# Schematic.net
KiCad netlist of a schematic drawn in EAGLE
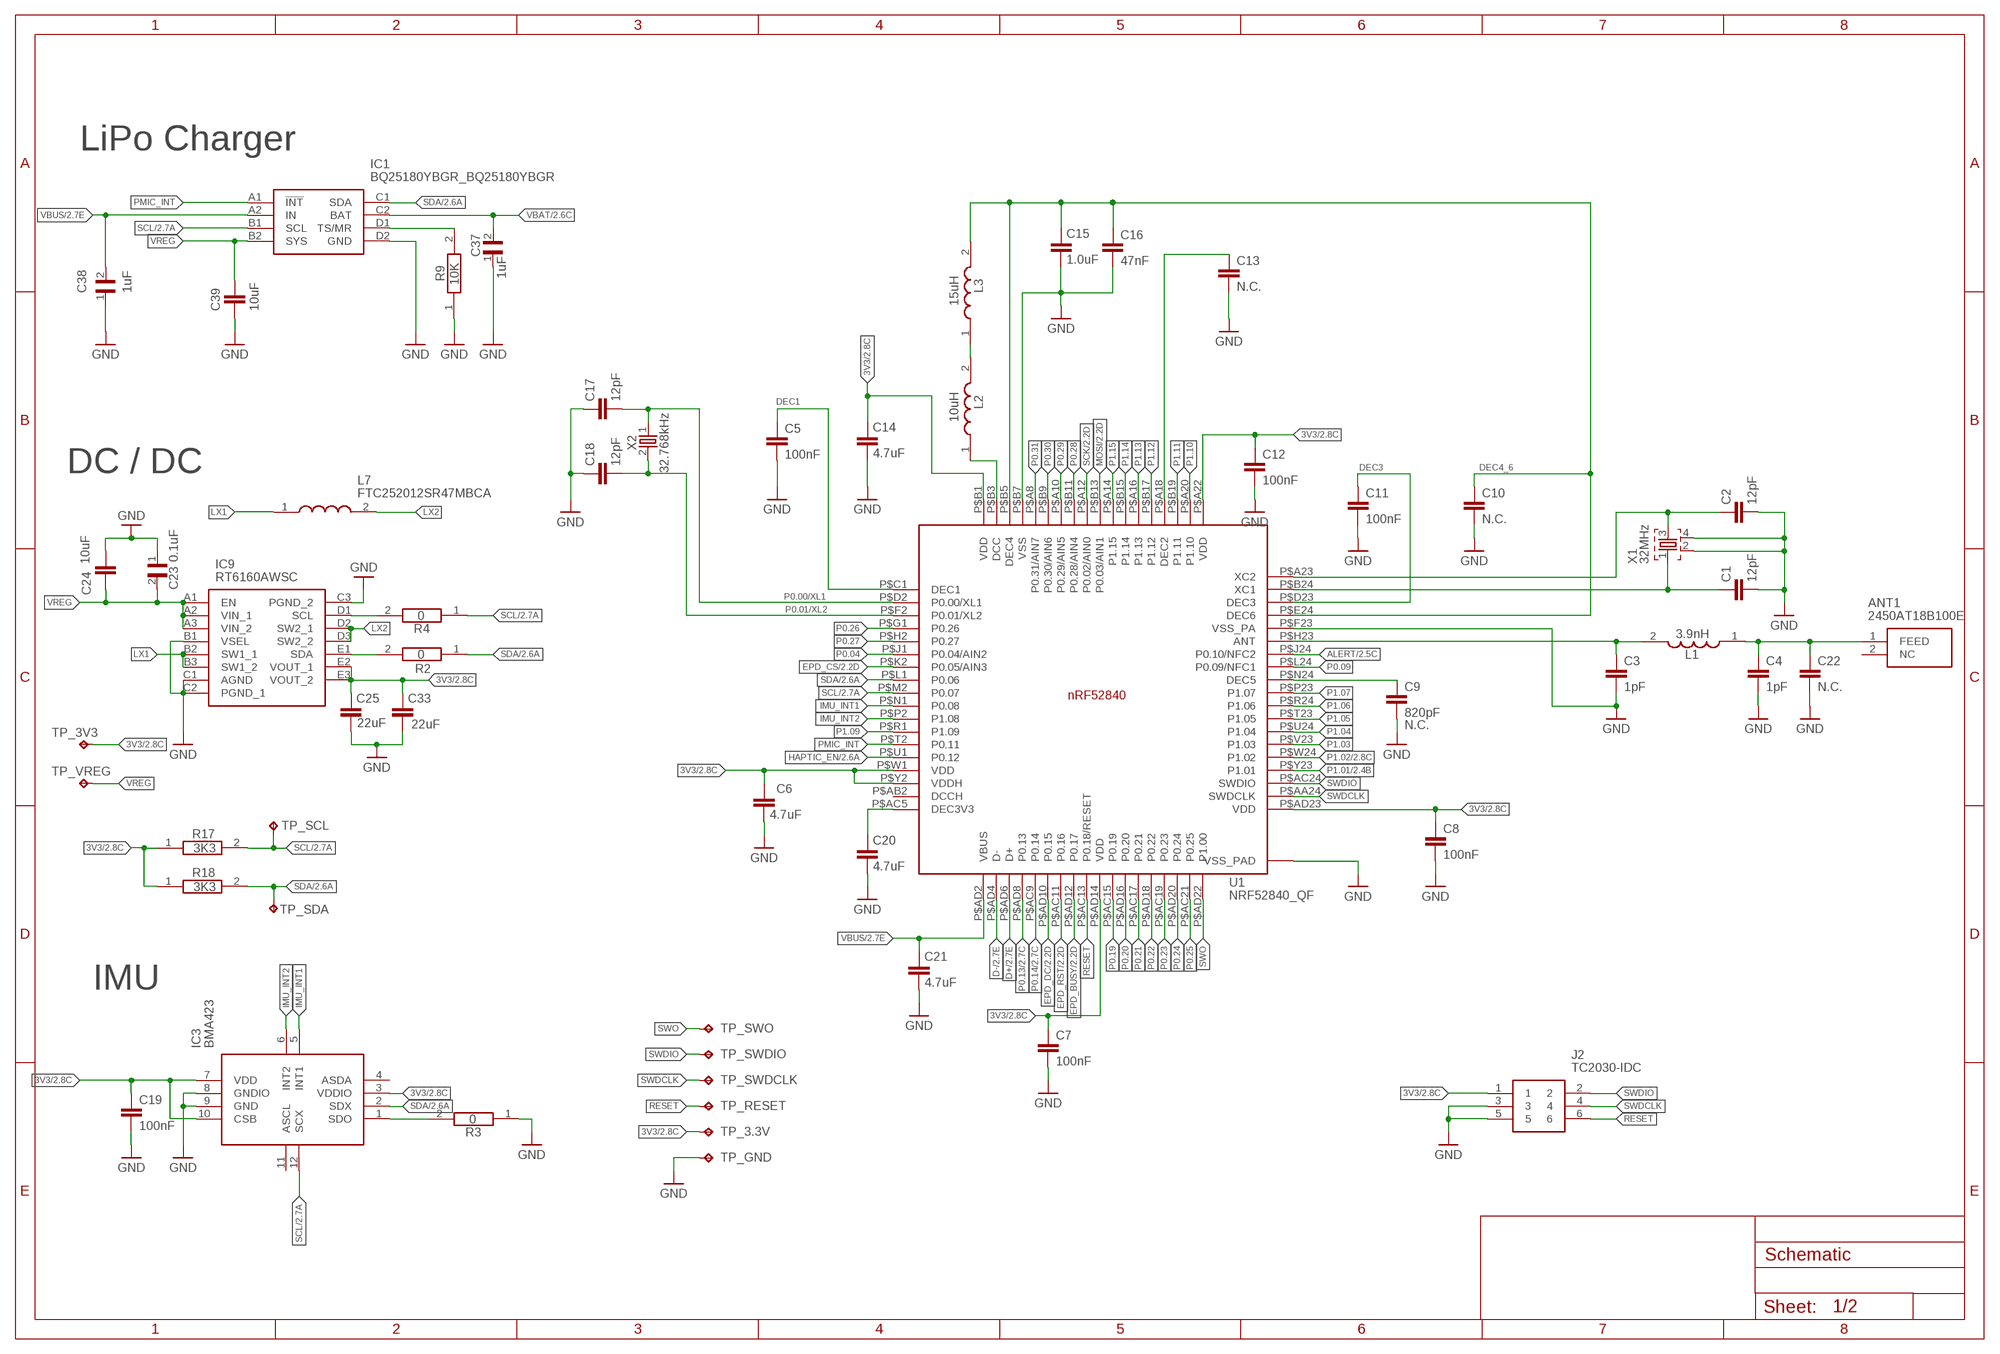
[diagram p0: schematic, sheet 1]
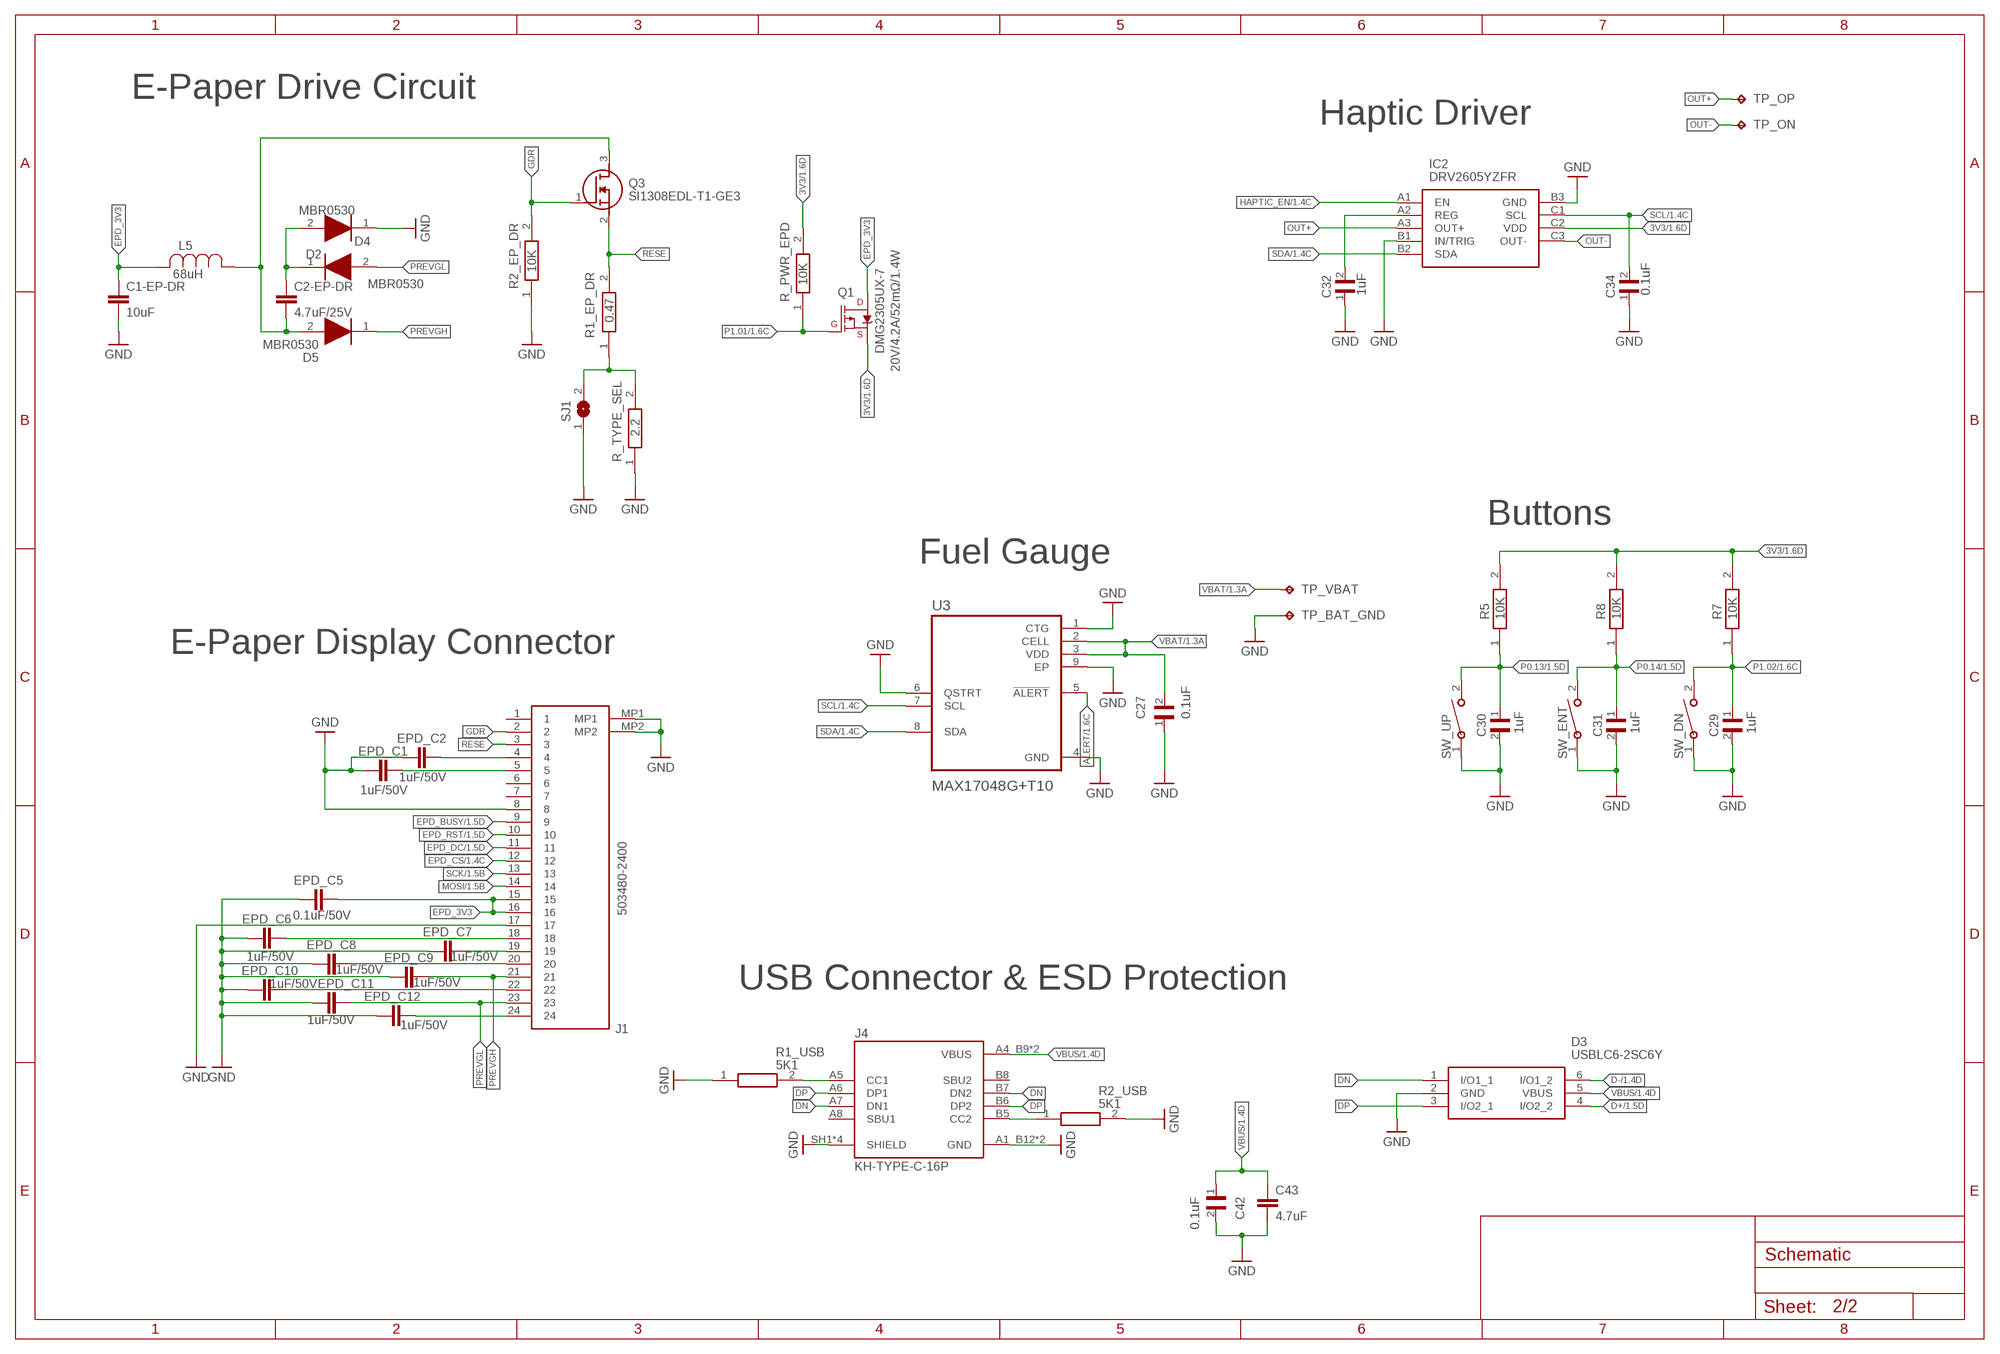
[diagram p1: schematic, sheet 2]

(export (version "E")
  (design (tool "Eeschema 10.0.6"))
  (components
    (comp (ref "C1-EP-DR")
      (value "10uF")
      (footprint "eagle-import:NORDIC_NRF_3_RESC0402_L")
      (libsource (lib "eagle-import") (part "NORDIC_NRF_3_CAPACITOR_0402_L"))
    )
    (comp (ref "C2-EP-DR")
      (value "4.7uF/25V")
      (footprint "eagle-import:NORDIC_NRF_3_RESC0402_L")
      (libsource (lib "eagle-import") (part "NORDIC_NRF_3_CAPACITOR_0402_L"))
    )
    (comp (ref "C27")
      (value "0.1uF")
      (footprint "eagle-import:GRM011R60J152KE01L_2_CAPC0201X13N")
      (fields (field (name "MF") "Murata") (field (name "MP") "GRM011R60J152KE01L"))
      (libsource (lib "eagle-import") (part "GRM011R60J152KE01L_2_GRM011R60J152KE01L"))
    )
    (comp (ref "C29")
      (value "1uF")
      (footprint "eagle-import:GRM011R60J152KE01L_1_0201")
      (libsource (lib "eagle-import") (part "GRM011R60J152KE01L_1_GRM011R60J152KE01L"))
    )
    (comp (ref "C30")
      (value "1uF")
      (footprint "eagle-import:GRM011R60J152KE01L_1_0201")
      (libsource (lib "eagle-import") (part "GRM011R60J152KE01L_1_GRM011R60J152KE01L"))
    )
    (comp (ref "C31")
      (value "1uF")
      (footprint "eagle-import:GRM011R60J152KE01L_1_0201")
      (libsource (lib "eagle-import") (part "GRM011R60J152KE01L_1_GRM011R60J152KE01L"))
    )
    (comp (ref "C32")
      (value "1uF")
      (footprint "eagle-import:GRM011R60J152KE01L_1_0201")
      (libsource (lib "eagle-import") (part "GRM011R60J152KE01L_1_GRM011R60J152KE01L"))
    )
    (comp (ref "C34")
      (value "0.1uF")
      (footprint "eagle-import:GRM011R60J152KE01L_1_0201")
      (libsource (lib "eagle-import") (part "GRM011R60J152KE01L_1_GRM011R60J152KE01L"))
    )
    (comp (ref "C42")
      (value "0.1uF")
      (footprint "eagle-import:GRM011R60J152KE01L_1_0201")
      (libsource (lib "eagle-import") (part "GRM011R60J152KE01L_1_GRM011R60J152KE01L"))
    )
    (comp (ref "C43")
      (value "4.7uF")
      (footprint "eagle-import:NORDIC_NRF_3_RESC0402_L")
      (libsource (lib "eagle-import") (part "NORDIC_NRF_3_CAPACITOR_0402_L"))
    )
    (comp (ref "D2")
      (value "MBR0530")
      (footprint "eagle-import:ESP32_C6_LIBRARY_5_SOD3716X135N")
      (fields (field (name "MF") "ON Semiconductor"))
      (libsource (lib "eagle-import") (part "ESP32_C6_LIBRARY_5_MBR0530"))
    )
    (comp (ref "D3")
      (value "USBLC6-2SC6Y")
      (footprint "eagle-import:ESP32_C6_LIBRARY_3_SOT95P280X145-6N")
      (fields (field (name "MF") "STMicroelectronics"))
      (libsource (lib "eagle-import") (part "ESP32_C6_LIBRARY_3_USBLC6-2SC6Y"))
    )
    (comp (ref "D4")
      (value "MBR0530")
      (footprint "eagle-import:ESP32_C6_LIBRARY_5_SOD3716X135N")
      (fields (field (name "MF") "ON Semiconductor"))
      (libsource (lib "eagle-import") (part "ESP32_C6_LIBRARY_5_MBR0530"))
    )
    (comp (ref "D5")
      (value "MBR0530")
      (footprint "eagle-import:ESP32_C6_LIBRARY_5_SOD3716X135N")
      (fields (field (name "MF") "ON Semiconductor"))
      (libsource (lib "eagle-import") (part "ESP32_C6_LIBRARY_5_MBR0530"))
    )
    (comp (ref "EPD_C1")
      (value "1uF/50V")
      (footprint "eagle-import:NORDIC_NRF_3_RESC0402_L")
      (libsource (lib "eagle-import") (part "NORDIC_NRF_3_CAPACITOR_0402_L"))
    )
    (comp (ref "EPD_C2")
      (value "1uF/50V")
      (footprint "eagle-import:NORDIC_NRF_3_RESC0402_L")
      (libsource (lib "eagle-import") (part "NORDIC_NRF_3_CAPACITOR_0402_L"))
    )
    (comp (ref "EPD_C5")
      (value "0.1uF/50V")
      (footprint "eagle-import:NORDIC_NRF_3_RESC0201_L")
      (libsource (lib "eagle-import") (part "NORDIC_NRF_3_CAPACITOR_0201_L"))
    )
    (comp (ref "EPD_C6")
      (value "1uF/50V")
      (footprint "eagle-import:NORDIC_NRF_3_RESC0402_L")
      (libsource (lib "eagle-import") (part "NORDIC_NRF_3_CAPACITOR_0402_L"))
    )
    (comp (ref "EPD_C7")
      (value "1uF/50V")
      (footprint "eagle-import:NORDIC_NRF_3_RESC0402_L")
      (libsource (lib "eagle-import") (part "NORDIC_NRF_3_CAPACITOR_0402_L"))
    )
    (comp (ref "EPD_C8")
      (value "1uF/50V")
      (footprint "eagle-import:NORDIC_NRF_3_RESC0402_L")
      (libsource (lib "eagle-import") (part "NORDIC_NRF_3_CAPACITOR_0402_L"))
    )
    (comp (ref "EPD_C9")
      (value "1uF/50V")
      (footprint "eagle-import:NORDIC_NRF_3_RESC0402_L")
      (libsource (lib "eagle-import") (part "NORDIC_NRF_3_CAPACITOR_0402_L"))
    )
    (comp (ref "EPD_C10")
      (value "1uF/50V")
      (footprint "eagle-import:NORDIC_NRF_3_RESC0402_L")
      (libsource (lib "eagle-import") (part "NORDIC_NRF_3_CAPACITOR_0402_L"))
    )
    (comp (ref "EPD_C11")
      (value "1uF/50V")
      (footprint "eagle-import:NORDIC_NRF_3_RESC0402_L")
      (libsource (lib "eagle-import") (part "NORDIC_NRF_3_CAPACITOR_0402_L"))
    )
    (comp (ref "EPD_C12")
      (value "1uF/50V")
      (footprint "eagle-import:NORDIC_NRF_3_RESC0402_L")
      (libsource (lib "eagle-import") (part "NORDIC_NRF_3_CAPACITOR_0402_L"))
    )
    (comp (ref "IC2")
      (value "DRV2605YZFR")
      (footprint "eagle-import:DRV2605YZFR_BGA9C50P3X3_144X144X62")
      (libsource (lib "eagle-import") (part "DRV2605YZFR_DRV2605YZFR"))
    )
    (comp (ref "J1")
      (value "503480-2400")
      (footprint "eagle-import:503480-2400_5034802400")
      (fields (field (name "MOUSER_PART_NUMBER") "538-503480-2400"))
      (libsource (lib "eagle-import") (part "503480-2400_503480-2400"))
    )
    (comp (ref "J4")
      (value "KH-TYPE-C-16P")
      (footprint "eagle-import:KH-TYPE-C-16P_KINGHELM_KH-TYPE-C-16P")
      (fields (field (name "MF") "kinghelm"))
      (libsource (lib "eagle-import") (part "KH-TYPE-C-16P_KH-TYPE-C-16P"))
    )
    (comp (ref "L5")
      (value "68uH")
      (footprint "eagle-import:ESP32_C6_LIBRARY_2_IND_4828-WE-TPC_WRE")
      (fields
        (field (name "MANUFACTURER_PART_NUMBER") "744043680")
        (field (name "COPYRIGHT") "Copyright (C) 2024 Ultra Librarian. All rights reserved.")
      )
      (libsource (lib "eagle-import") (part "ESP32_C6_LIBRARY_2_744043680IND_4828-WE-TPC_WRE"))
    )
    (comp (ref "Q1")
      (value "20V/4.2A/52mΩ/1.4W")
      (footprint "eagle-import:ESP32_C6_LIBRARY_4_ESP32_C6_LIBRARY_4_ESP32_C6_LIBRARY_4_ESP32_C6_LIBRARY_4_ESP32_WROVER_SPARKFUN-DISCRETESEMI_SOT23-3")
      (libsource (lib "eagle-import") (part "ESP32_C6_LIBRARY_4_ESP32_WROVER_SPARKFUN-DISCRETESEMI_MOSFET_PCH-DMG2305UX-7"))
    )
    (comp (ref "Q3")
      (value "SI1308EDL-T1-GE3")
      (footprint "eagle-import:ESP32_C6_LIBRARY_6_SOT65P210X110-3N")
      (fields (field (name "MF") "Vishay Siliconix"))
      (libsource (lib "eagle-import") (part "ESP32_C6_LIBRARY_6_SI1308EDL-T1-GE3"))
    )
    (comp (ref "R1_EP_DR")
      (value "0.47")
      (footprint "eagle-import:ERA-1AEB3401C_0201")
      (libsource (lib "eagle-import") (part "ERA-1AEB3401C_CPF0201D7K68C1"))
    )
    (comp (ref "R1_USB")
      (value "5K1")
      (footprint "eagle-import:ERA-1AEB3401C_0201")
      (libsource (lib "eagle-import") (part "ERA-1AEB3401C_CPF0201D7K68C1"))
    )
    (comp (ref "R2_EP_DR")
      (value "10K")
      (footprint "eagle-import:ERA-1AEB3401C_0201")
      (libsource (lib "eagle-import") (part "ERA-1AEB3401C_CPF0201D7K68C1"))
    )
    (comp (ref "R2_USB")
      (value "5K1")
      (footprint "eagle-import:ERA-1AEB3401C_0201")
      (libsource (lib "eagle-import") (part "ERA-1AEB3401C_CPF0201D7K68C1"))
    )
    (comp (ref "R5")
      (value "10K")
      (footprint "eagle-import:ERA-1AEB3401C_0201")
      (libsource (lib "eagle-import") (part "ERA-1AEB3401C_CPF0201D7K68C1"))
    )
    (comp (ref "R7")
      (value "10K")
      (footprint "eagle-import:ERA-1AEB3401C_0201")
      (libsource (lib "eagle-import") (part "ERA-1AEB3401C_CPF0201D7K68C1"))
    )
    (comp (ref "R8")
      (value "10K")
      (footprint "eagle-import:ERA-1AEB3401C_0201")
      (libsource (lib "eagle-import") (part "ERA-1AEB3401C_CPF0201D7K68C1"))
    )
    (comp (ref "R_PWR_EPD")
      (value "10K")
      (footprint "eagle-import:ERA-1AEB3401C_0201")
      (libsource (lib "eagle-import") (part "ERA-1AEB3401C_CPF0201D7K68C1"))
    )
    (comp (ref "R_TYPE_SEL")
      (value "2.2")
      (footprint "eagle-import:ERA-1AEB3401C_0201")
      (libsource (lib "eagle-import") (part "ERA-1AEB3401C_CPF0201D7K68C1"))
    )
    (comp (ref "SJ1")
      (value "ESP32_C6_LIBRARY_7_JUMPER_SJ")
      (footprint "eagle-import:ESP32_C6_LIBRARY_7_JUMPER_SJ")
      (libsource (lib "eagle-import") (part "ESP32_C6_LIBRARY_7_JUMPER_SJ"))
    )
    (comp (ref "SW_DN")
      (value "2025-10-22_07-23-44_LIBRARY_EVP-AKE31ASW_EVP-AKE31A_PAN")
      (footprint "eagle-import:2025-10-22_07-23-44_LIBRARY_SW_EVP-AKE31A_PAN")
      (fields
        (field (name "MANUFACTURER_PART_NUMBER") "EVP-AKE31A")
        (field (name "COPYRIGHT") "Copyright (C) 2025 Ultra Librarian. All rights reserved.")
      )
      (libsource (lib "eagle-import") (part "2025-10-22_07-23-44_LIBRARY_EVP-AKE31ASW_EVP-AKE31A_PAN"))
    )
    (comp (ref "SW_ENT")
      (value "2025-10-22_07-23-44_LIBRARY_EVP-AKE31ASW_EVP-AKE31A_PAN")
      (footprint "eagle-import:2025-10-22_07-23-44_LIBRARY_SW_EVP-AKE31A_PAN")
      (fields
        (field (name "MANUFACTURER_PART_NUMBER") "EVP-AKE31A")
        (field (name "COPYRIGHT") "Copyright (C) 2025 Ultra Librarian. All rights reserved.")
      )
      (libsource (lib "eagle-import") (part "2025-10-22_07-23-44_LIBRARY_EVP-AKE31ASW_EVP-AKE31A_PAN"))
    )
    (comp (ref "SW_UP")
      (value "2025-10-22_07-23-44_LIBRARY_EVP-AKE31ASW_EVP-AKE31A_PAN")
      (footprint "eagle-import:2025-10-22_07-23-44_LIBRARY_SW_EVP-AKE31A_PAN")
      (fields
        (field (name "MANUFACTURER_PART_NUMBER") "EVP-AKE31A")
        (field (name "COPYRIGHT") "Copyright (C) 2025 Ultra Librarian. All rights reserved.")
      )
      (libsource (lib "eagle-import") (part "2025-10-22_07-23-44_LIBRARY_EVP-AKE31ASW_EVP-AKE31A_PAN"))
    )
    (comp (ref "TP_BAT_GND")
      (value "HECTOR_WATCH_1_TPTP20R")
      (footprint "eagle-import:HECTOR_WATCH_1_TP20R")
      (libsource (lib "eagle-import") (part "HECTOR_WATCH_1_TPTP20R"))
    )
    (comp (ref "TP_ON")
      (value "HECTOR_WATCH_1_TPTP20R")
      (footprint "eagle-import:HECTOR_WATCH_1_TP20R")
      (libsource (lib "eagle-import") (part "HECTOR_WATCH_1_TPTP20R"))
    )
    (comp (ref "TP_OP")
      (value "HECTOR_WATCH_1_TPTP20R")
      (footprint "eagle-import:HECTOR_WATCH_1_TP20R")
      (libsource (lib "eagle-import") (part "HECTOR_WATCH_1_TPTP20R"))
    )
    (comp (ref "TP_VBAT")
      (value "HECTOR_WATCH_1_TPTP20R")
      (footprint "eagle-import:HECTOR_WATCH_1_TP20R")
      (libsource (lib "eagle-import") (part "HECTOR_WATCH_1_TPTP20R"))
    )
    (comp (ref "U3")
      (value "MAX17048G+T10")
      (footprint "eagle-import:ESP32_C6_LIBRARY_SON50P200X200X80-9N")
      (fields (field (name "MF") "Analog Devices"))
      (libsource (lib "eagle-import") (part "ESP32_C6_LIBRARY_MAX17048G+T10"))
    )
    (comp (ref "ANT1")
      (value "2450AT18B100E")
      (footprint "eagle-import:2450AT18B100E_ANTC3216X140N")
      (fields (field (name "MOUSER_PART_NUMBER") "609-2450AT18B100E"))
      (libsource (lib "eagle-import") (part "2450AT18B100E_2450AT18B100E"))
    )
    (comp (ref "C1")
      (value "12pF")
      (footprint "eagle-import:NORDIC_NRF_3_RESC0201_L")
      (libsource (lib "eagle-import") (part "NORDIC_NRF_3_CAPACITOR_0201_L"))
    )
    (comp (ref "C2")
      (value "12pF")
      (footprint "eagle-import:NORDIC_NRF_3_RESC0201_L")
      (libsource (lib "eagle-import") (part "NORDIC_NRF_3_CAPACITOR_0201_L"))
    )
    (comp (ref "C3")
      (value "1pF")
      (footprint "eagle-import:NORDIC_NRF_3_RESC0201_L")
      (libsource (lib "eagle-import") (part "NORDIC_NRF_3_CAPACITOR_0201_L"))
    )
    (comp (ref "C4")
      (value "1pF")
      (footprint "eagle-import:NORDIC_NRF_3_RESC0201_L")
      (libsource (lib "eagle-import") (part "NORDIC_NRF_3_CAPACITOR_0201_L"))
    )
    (comp (ref "C5")
      (value "100nF")
      (footprint "eagle-import:NORDIC_NRF_3_RESC0201_L")
      (libsource (lib "eagle-import") (part "NORDIC_NRF_3_CAPACITOR_0201_L"))
    )
    (comp (ref "C6")
      (value "4.7uF")
      (footprint "eagle-import:NORDIC_NRF_3_RESC0402_L")
      (libsource (lib "eagle-import") (part "NORDIC_NRF_3_CAPACITOR_0402_L"))
    )
    (comp (ref "C7")
      (value "100nF")
      (footprint "eagle-import:NORDIC_NRF_3_RESC0201_L")
      (libsource (lib "eagle-import") (part "NORDIC_NRF_3_CAPACITOR_0201_L"))
    )
    (comp (ref "C8")
      (value "100nF")
      (footprint "eagle-import:NORDIC_NRF_3_RESC0201_L")
      (libsource (lib "eagle-import") (part "NORDIC_NRF_3_CAPACITOR_0201_L"))
    )
    (comp (ref "C9")
      (value "820pF")
      (footprint "eagle-import:NORDIC_NRF_3_RESC0201_L")
      (libsource (lib "eagle-import") (part "NORDIC_NRF_3_CAPACITOR_0201_L"))
    )
    (comp (ref "C10")
      (value "N.C.")
      (footprint "eagle-import:NORDIC_NRF_3_RESC0201_L")
      (libsource (lib "eagle-import") (part "NORDIC_NRF_3_CAPACITOR_0201_L"))
    )
    (comp (ref "C11")
      (value "100nF")
      (footprint "eagle-import:NORDIC_NRF_3_RESC0201_L")
      (libsource (lib "eagle-import") (part "NORDIC_NRF_3_CAPACITOR_0201_L"))
    )
    (comp (ref "C12")
      (value "100nF")
      (footprint "eagle-import:NORDIC_NRF_3_RESC0201_L")
      (libsource (lib "eagle-import") (part "NORDIC_NRF_3_CAPACITOR_0201_L"))
    )
    (comp (ref "C13")
      (value "N.C.")
      (footprint "eagle-import:NORDIC_NRF_3_RESC0201_L")
      (libsource (lib "eagle-import") (part "NORDIC_NRF_3_CAPACITOR_0201_L"))
    )
    (comp (ref "C14")
      (value "4.7uF")
      (footprint "eagle-import:NORDIC_NRF_3_RESC0402_L")
      (libsource (lib "eagle-import") (part "NORDIC_NRF_3_CAPACITOR_0402_L"))
    )
    (comp (ref "C15")
      (value "1.0uF")
      (footprint "eagle-import:NORDIC_NRF_3_RESC0402_L")
      (libsource (lib "eagle-import") (part "NORDIC_NRF_3_CAPACITOR_0402_L"))
    )
    (comp (ref "C16")
      (value "47nF")
      (footprint "eagle-import:NORDIC_NRF_3_RESC0201_L")
      (libsource (lib "eagle-import") (part "NORDIC_NRF_3_CAPACITOR_0201_L"))
    )
    (comp (ref "C17")
      (value "12pF")
      (footprint "eagle-import:NORDIC_NRF_3_RESC0201_L")
      (libsource (lib "eagle-import") (part "NORDIC_NRF_3_CAPACITOR_0201_L"))
    )
    (comp (ref "C18")
      (value "12pF")
      (footprint "eagle-import:NORDIC_NRF_3_RESC0201_L")
      (libsource (lib "eagle-import") (part "NORDIC_NRF_3_CAPACITOR_0201_L"))
    )
    (comp (ref "C19")
      (value "100nF")
      (footprint "eagle-import:NORDIC_NRF_3_RESC0201_L")
      (libsource (lib "eagle-import") (part "NORDIC_NRF_3_CAPACITOR_0201_L"))
    )
    (comp (ref "C20")
      (value "4.7uF")
      (footprint "eagle-import:NORDIC_NRF_3_RESC0402_L")
      (libsource (lib "eagle-import") (part "NORDIC_NRF_3_CAPACITOR_0402_L"))
    )
    (comp (ref "C21")
      (value "4.7uF")
      (footprint "eagle-import:NORDIC_NRF_3_RESC0402_L")
      (libsource (lib "eagle-import") (part "NORDIC_NRF_3_CAPACITOR_0402_L"))
    )
    (comp (ref "C22")
      (value "N.C.")
      (footprint "eagle-import:NORDIC_NRF_3_RESC0201_L")
      (libsource (lib "eagle-import") (part "NORDIC_NRF_3_CAPACITOR_0201_L"))
    )
    (comp (ref "C23")
      (value "0.1uF")
      (footprint "eagle-import:GRM011R60J152KE01L_2_CAPC0201X13N")
      (fields (field (name "MF") "Murata") (field (name "MP") "GRM011R60J152KE01L"))
      (libsource (lib "eagle-import") (part "GRM011R60J152KE01L_2_GRM011R60J152KE01L"))
    )
    (comp (ref "C24")
      (value "10uF")
      (footprint "eagle-import:NORDIC_NRF_3_RESC0402_L")
      (libsource (lib "eagle-import") (part "NORDIC_NRF_3_CAPACITOR_0402_L"))
    )
    (comp (ref "C25")
      (value "22uF")
      (footprint "eagle-import:NORDIC_NRF_3_RESC0402_L")
      (libsource (lib "eagle-import") (part "NORDIC_NRF_3_CAPACITOR_0402_L"))
    )
    (comp (ref "C33")
      (value "22uF")
      (footprint "eagle-import:NORDIC_NRF_3_RESC0402_L")
      (libsource (lib "eagle-import") (part "NORDIC_NRF_3_CAPACITOR_0402_L"))
    )
    (comp (ref "C37")
      (value "1uF")
      (footprint "eagle-import:GRM011R60J152KE01L_2_CAPC0201X13N")
      (fields (field (name "MF") "Murata") (field (name "MP") "GRM011R60J152KE01L"))
      (libsource (lib "eagle-import") (part "GRM011R60J152KE01L_2_GRM011R60J152KE01L"))
    )
    (comp (ref "C38")
      (value "1uF")
      (footprint "eagle-import:GRM011R60J152KE01L_2_CAPC0201X13N")
      (fields (field (name "MF") "Murata") (field (name "MP") "GRM011R60J152KE01L"))
      (libsource (lib "eagle-import") (part "GRM011R60J152KE01L_2_GRM011R60J152KE01L"))
    )
    (comp (ref "C39")
      (value "10uF")
      (footprint "eagle-import:NORDIC_NRF_3_RESC0402_L")
      (libsource (lib "eagle-import") (part "NORDIC_NRF_3_CAPACITOR_0402_L"))
    )
    (comp (ref "IC1")
      (value "BQ25180YBGR_BQ25180YBGR")
      (footprint "eagle-import:BQ25180YBGR_BGA8C40P2X4_100X155X50")
      (fields
        (field (name "ARROW_PART_NUMBER") "BQ25180YBGR")
        (field (name "MOUSER_PART_NUMBER") "595-BQ25180YBGR")
      )
      (libsource (lib "eagle-import") (part "BQ25180YBGR_BQ25180YBGR"))
    )
    (comp (ref "IC3")
      (value "BMA423")
      (footprint "eagle-import:BMA423_BMA423")
      (fields (field (name "MOUSER_PART_NUMBER") "262-BMA423"))
      (libsource (lib "eagle-import") (part "BMA423_BMA423"))
    )
    (comp (ref "IC9")
      (value "RT6160AWSC")
      (footprint "eagle-import:RT6160AWSC_BGA15C40P3X5_140X230X60")
      (fields (field (name "MOUSER_PART_NUMBER") "835-RT6160AWSC"))
      (libsource (lib "eagle-import") (part "RT6160AWSC_RT6160AWSC"))
    )
    (comp (ref "J2")
      (value "TC2030-IDC")
      (footprint "eagle-import:TC2030-IDC_TC2030IDC")
      (libsource (lib "eagle-import") (part "TC2030-IDC_TC2030-IDC"))
    )
    (comp (ref "L1")
      (value "3.9nH")
      (footprint "eagle-import:MLP2016SR47MT0S1_INDC2016X100N")
      (fields (field (name "MANUFACTURER_PART_NUMBER") "FTC252012SR47MBCA"))
      (libsource (lib "eagle-import") (part "MLP2016SR47MT0S1_FTC252012SR47MBCA"))
    )
    (comp (ref "L2")
      (value "10uH")
      (footprint "eagle-import:MLP2016SR47MT0S1_INDC2016X100N")
      (fields (field (name "MANUFACTURER_PART_NUMBER") "FTC252012SR47MBCA"))
      (libsource (lib "eagle-import") (part "MLP2016SR47MT0S1_FTC252012SR47MBCA"))
    )
    (comp (ref "L3")
      (value "15uH")
      (footprint "eagle-import:MLP2016SR47MT0S1_INDC2016X100N")
      (fields (field (name "MANUFACTURER_PART_NUMBER") "FTC252012SR47MBCA"))
      (libsource (lib "eagle-import") (part "MLP2016SR47MT0S1_FTC252012SR47MBCA"))
    )
    (comp (ref "L7")
      (value "FTC252012SR47MBCA")
      (footprint "eagle-import:MLP2016SR47MT0S1_INDC2016X100N")
      (libsource (lib "eagle-import") (part "MLP2016SR47MT0S1_FTC252012SR47MBCA"))
    )
    (comp (ref "R2")
      (value "0")
      (footprint "eagle-import:ERA-1AEB3401C_0201")
      (libsource (lib "eagle-import") (part "ERA-1AEB3401C_CPF0201D7K68C1"))
    )
    (comp (ref "R3")
      (value "0")
      (footprint "eagle-import:ERA-1AEB3401C_0201")
      (libsource (lib "eagle-import") (part "ERA-1AEB3401C_CPF0201D7K68C1"))
    )
    (comp (ref "R4")
      (value "0")
      (footprint "eagle-import:ERA-1AEB3401C_0201")
      (libsource (lib "eagle-import") (part "ERA-1AEB3401C_CPF0201D7K68C1"))
    )
    (comp (ref "R9")
      (value "10K")
      (footprint "eagle-import:ERA-1AEB3401C_0201")
      (libsource (lib "eagle-import") (part "ERA-1AEB3401C_CPF0201D7K68C1"))
    )
    (comp (ref "R17")
      (value "3K3")
      (footprint "eagle-import:ERA-1AEB3401C_0201")
      (libsource (lib "eagle-import") (part "ERA-1AEB3401C_CPF0201D7K68C1"))
    )
    (comp (ref "R18")
      (value "3K3")
      (footprint "eagle-import:ERA-1AEB3401C_0201")
      (libsource (lib "eagle-import") (part "ERA-1AEB3401C_CPF0201D7K68C1"))
    )
    (comp (ref "TP_3.3V")
      (value "HECTOR_WATCH_1_TPTP20R")
      (footprint "eagle-import:HECTOR_WATCH_1_TP20R")
      (libsource (lib "eagle-import") (part "HECTOR_WATCH_1_TPTP20R"))
    )
    (comp (ref "TP_3V3")
      (value "HECTOR_WATCH_1_TPTP20R")
      (footprint "eagle-import:HECTOR_WATCH_1_TP20R")
      (libsource (lib "eagle-import") (part "HECTOR_WATCH_1_TPTP20R"))
    )
    (comp (ref "TP_GND")
      (value "HECTOR_WATCH_1_TPTP20R")
      (footprint "eagle-import:HECTOR_WATCH_1_TP20R")
      (libsource (lib "eagle-import") (part "HECTOR_WATCH_1_TPTP20R"))
    )
    (comp (ref "TP_RESET")
      (value "HECTOR_WATCH_1_TPTP20R")
      (footprint "eagle-import:HECTOR_WATCH_1_TP20R")
      (libsource (lib "eagle-import") (part "HECTOR_WATCH_1_TPTP20R"))
    )
    (comp (ref "TP_SCL")
      (value "HECTOR_WATCH_1_TPTP20R")
      (footprint "eagle-import:HECTOR_WATCH_1_TP20R")
      (libsource (lib "eagle-import") (part "HECTOR_WATCH_1_TPTP20R"))
    )
    (comp (ref "TP_SDA")
      (value "HECTOR_WATCH_1_TPTP20R")
      (footprint "eagle-import:HECTOR_WATCH_1_TP20R")
      (libsource (lib "eagle-import") (part "HECTOR_WATCH_1_TPTP20R"))
    )
    (comp (ref "TP_SWDCLK")
      (value "HECTOR_WATCH_1_TPTP20R")
      (footprint "eagle-import:HECTOR_WATCH_1_TP20R")
      (libsource (lib "eagle-import") (part "HECTOR_WATCH_1_TPTP20R"))
    )
    (comp (ref "TP_SWDIO")
      (value "HECTOR_WATCH_1_TPTP20R")
      (footprint "eagle-import:HECTOR_WATCH_1_TP20R")
      (libsource (lib "eagle-import") (part "HECTOR_WATCH_1_TPTP20R"))
    )
    (comp (ref "TP_SWO")
      (value "HECTOR_WATCH_1_TPTP20R")
      (footprint "eagle-import:HECTOR_WATCH_1_TP20R")
      (libsource (lib "eagle-import") (part "HECTOR_WATCH_1_TPTP20R"))
    )
    (comp (ref "TP_VREG")
      (value "HECTOR_WATCH_1_TPTP20R")
      (footprint "eagle-import:HECTOR_WATCH_1_TP20R")
      (libsource (lib "eagle-import") (part "HECTOR_WATCH_1_TPTP20R"))
    )
    (comp (ref "U1")
      (value "NRF52840_QF")
      (footprint "eagle-import:NORDIC_NRF_4_AQFN50P700X700X85_HS-74N")
      (libsource (lib "eagle-import") (part "NORDIC_NRF_4_NRF52840_QF"))
    )
    (comp (ref "X1")
      (value "32MHz")
      (footprint "eagle-import:NORDIC_NRF_BT-XTAL_2016_N")
      (libsource (lib "eagle-import") (part "NORDIC_NRF_XTAL_32MHZ"))
    )
    (comp (ref "X2")
      (value "32.768kHz")
      (footprint "eagle-import:NORDIC_NRF_1_XTAL_3215_N")
      (libsource (lib "eagle-import") (part "NORDIC_NRF_1_XTAL_32KHZ"))
    )
  )
  (nets
    (net (code "1") (name "3V3") (class "Default")
      (node (ref "C12") (pin "1") (pinfunction "1_1") (pintype "passive"))
      (node (ref "C14") (pin "1") (pinfunction "1_1") (pintype "passive"))
      (node (ref "C19") (pin "1") (pinfunction "1_1") (pintype "passive"))
      (node (ref "C25") (pin "1") (pinfunction "1_1") (pintype "passive"))
      (node (ref "C33") (pin "1") (pinfunction "1_1") (pintype "passive"))
      (node (ref "C6") (pin "1") (pinfunction "1_1") (pintype "passive"))
      (node (ref "C7") (pin "1") (pinfunction "1_1") (pintype "passive"))
      (node (ref "C8") (pin "1") (pinfunction "1_1") (pintype "passive"))
      (node (ref "IC2") (pin "C2") (pinfunction "VDD_C2") (pintype "bidirectional"))
      (node (ref "IC3") (pin "10") (pinfunction "CSB_10") (pintype "bidirectional"))
      (node (ref "IC3") (pin "3") (pinfunction "VDDIO_3") (pintype "bidirectional"))
      (node (ref "IC3") (pin "7") (pinfunction "VDD_7") (pintype "bidirectional"))
      (node (ref "IC9") (pin "E2") (pinfunction "VOUT_1_E2") (pintype "bidirectional"))
      (node (ref "IC9") (pin "E3") (pinfunction "VOUT_2_E3") (pintype "bidirectional"))
      (node (ref "J2") (pin "1") (pinfunction "1_1") (pintype "bidirectional"))
      (node (ref "Q1") (pin "2") (pinfunction "S_2") (pintype "bidirectional"))
      (node (ref "R17") (pin "1") (pinfunction "1_1") (pintype "bidirectional"))
      (node (ref "R18") (pin "1") (pinfunction "1_1") (pintype "bidirectional"))
      (node (ref "R5") (pin "2") (pinfunction "2_2") (pintype "bidirectional"))
      (node (ref "R7") (pin "2") (pinfunction "2_2") (pintype "bidirectional"))
      (node (ref "R8") (pin "2") (pinfunction "2_2") (pintype "bidirectional"))
      (node (ref "R_PWR_EPD") (pin "2") (pinfunction "2_2") (pintype "bidirectional"))
      (node (ref "TP_3.3V") (pin "TP") (pinfunction "TP_TP") (pintype "input"))
      (node (ref "TP_3V3") (pin "TP") (pinfunction "TP_TP") (pintype "input"))
      (node (ref "U1") (pin "P$A22") (pinfunction "VDD_P$A22") (pintype "power_in"))
      (node (ref "U1") (pin "P$AD14") (pinfunction "VDD_P$AD14") (pintype "power_in"))
      (node (ref "U1") (pin "P$AD23") (pinfunction "VDD_P$AD23") (pintype "power_in"))
      (node (ref "U1") (pin "P$B1") (pinfunction "VDD_P$B1") (pintype "power_in"))
      (node (ref "U1") (pin "P$W1") (pinfunction "VDD_P$W1") (pintype "power_in"))
      (node (ref "U1") (pin "P$Y2") (pinfunction "VDDH_P$Y2") (pintype "power_in"))
    )
    (net (code "2") (name "ALERT") (class "Default")
      (node (ref "U1") (pin "P$J24") (pinfunction "P0.10/NFC2_P$J24") (pintype "bidirectional"))
      (node (ref "U3") (pin "5") (pinfunction "~{ALERT}_5") (pintype "output"))
    )
    (net (code "3") (name "D+") (class "Default")
      (node (ref "D3") (pin "4") (pinfunction "I/O2_2_4") (pintype "bidirectional"))
      (node (ref "U1") (pin "P$AD6") (pinfunction "D+_P$AD6") (pintype "bidirectional"))
    )
    (net (code "4") (name "D-") (class "Default")
      (node (ref "D3") (pin "6") (pinfunction "I/O1_2_6") (pintype "bidirectional"))
      (node (ref "U1") (pin "P$AD4") (pinfunction "D-_P$AD4") (pintype "bidirectional"))
    )
    (net (code "5") (name "DEC1") (class "Default")
      (node (ref "C5") (pin "1") (pinfunction "1_1") (pintype "passive"))
      (node (ref "U1") (pin "P$C1") (pinfunction "DEC1_P$C1") (pintype "power_in"))
    )
    (net (code "6") (name "DEC3") (class "Default")
      (node (ref "C11") (pin "1") (pinfunction "1_1") (pintype "passive"))
      (node (ref "U1") (pin "P$D23") (pinfunction "DEC3_P$D23") (pintype "bidirectional"))
    )
    (net (code "7") (name "DEC4_6") (class "Default")
      (node (ref "C10") (pin "1") (pinfunction "1_1") (pintype "passive"))
      (node (ref "C15") (pin "1") (pinfunction "1_1") (pintype "passive"))
      (node (ref "C16") (pin "1") (pinfunction "1_1") (pintype "passive"))
      (node (ref "L3") (pin "2") (pinfunction "2_2") (pintype "bidirectional"))
      (node (ref "U1") (pin "P$B5") (pinfunction "DEC4_P$B5") (pintype "power_in"))
      (node (ref "U1") (pin "P$E24") (pinfunction "DEC6_P$E24") (pintype "bidirectional"))
    )
    (net (code "8") (name "DN") (class "Default")
      (node (ref "D3") (pin "1") (pinfunction "I/O1_1_1") (pintype "bidirectional"))
      (node (ref "J4") (pin "A7") (pinfunction "DN1_A7") (pintype "bidirectional"))
      (node (ref "J4") (pin "B7") (pinfunction "DN2_B7") (pintype "bidirectional"))
    )
    (net (code "9") (name "DP") (class "Default")
      (node (ref "D3") (pin "3") (pinfunction "I/O2_1_3") (pintype "bidirectional"))
      (node (ref "J4") (pin "A6") (pinfunction "DP1_A6") (pintype "bidirectional"))
      (node (ref "J4") (pin "B6") (pinfunction "DP2_B6") (pintype "bidirectional"))
    )
    (net (code "10") (name "EPD_3V3") (class "Default")
      (node (ref "C1-EP-DR") (pin "1") (pinfunction "1_1") (pintype "passive"))
      (node (ref "EPD_C5") (pin "2") (pinfunction "2_2") (pintype "passive"))
      (node (ref "J1") (pin "15") (pinfunction "15_15") (pintype "bidirectional"))
      (node (ref "J1") (pin "16") (pinfunction "16_16") (pintype "bidirectional"))
      (node (ref "L5") (pin "2") (pinfunction "2_2") (pintype "passive"))
      (node (ref "Q1") (pin "3") (pinfunction "D_3") (pintype "bidirectional"))
    )
    (net (code "11") (name "EPD_BUSY") (class "Default")
      (node (ref "J1") (pin "9") (pinfunction "9_9") (pintype "bidirectional"))
      (node (ref "U1") (pin "P$AD12") (pinfunction "P0.17_P$AD12") (pintype "bidirectional"))
    )
    (net (code "12") (name "EPD_CS") (class "Default")
      (node (ref "J1") (pin "12") (pinfunction "12_12") (pintype "bidirectional"))
      (node (ref "U1") (pin "P$K2") (pinfunction "P0.05/AIN3_P$K2") (pintype "bidirectional"))
    )
    (net (code "13") (name "EPD_DC") (class "Default")
      (node (ref "J1") (pin "11") (pinfunction "11_11") (pintype "bidirectional"))
      (node (ref "U1") (pin "P$AD10") (pinfunction "P0.15_P$AD10") (pintype "bidirectional"))
    )
    (net (code "14") (name "EPD_RST") (class "Default")
      (node (ref "J1") (pin "10") (pinfunction "10_10") (pintype "bidirectional"))
      (node (ref "U1") (pin "P$AC11") (pinfunction "P0.16_P$AC11") (pintype "bidirectional"))
    )
    (net (code "15") (name "GDR") (class "Default")
      (node (ref "J1") (pin "2") (pinfunction "2_2") (pintype "bidirectional"))
      (node (ref "Q3") (pin "1") (pinfunction "G_1") (pintype "bidirectional"))
      (node (ref "R2_EP_DR") (pin "2") (pinfunction "2_2") (pintype "bidirectional"))
    )
    (net (code "16") (name "GND") (class "Default")
      (node (ref "C1") (pin "2") (pinfunction "2_2") (pintype "passive"))
      (node (ref "C1-EP-DR") (pin "2") (pinfunction "2_2") (pintype "passive"))
      (node (ref "C10") (pin "2") (pinfunction "2_2") (pintype "passive"))
      (node (ref "C11") (pin "2") (pinfunction "2_2") (pintype "passive"))
      (node (ref "C12") (pin "2") (pinfunction "2_2") (pintype "passive"))
      (node (ref "C13") (pin "2") (pinfunction "2_2") (pintype "passive"))
      (node (ref "C14") (pin "2") (pinfunction "2_2") (pintype "passive"))
      (node (ref "C15") (pin "2") (pinfunction "2_2") (pintype "passive"))
      (node (ref "C16") (pin "2") (pinfunction "2_2") (pintype "passive"))
      (node (ref "C17") (pin "1") (pinfunction "1_1") (pintype "passive"))
      (node (ref "C18") (pin "1") (pinfunction "1_1") (pintype "passive"))
      (node (ref "C19") (pin "2") (pinfunction "2_2") (pintype "passive"))
      (node (ref "C2") (pin "2") (pinfunction "2_2") (pintype "passive"))
      (node (ref "C20") (pin "2") (pinfunction "2_2") (pintype "passive"))
      (node (ref "C21") (pin "2") (pinfunction "2_2") (pintype "passive"))
      (node (ref "C22") (pin "2") (pinfunction "2_2") (pintype "passive"))
      (node (ref "C23") (pin "1") (pinfunction "1_1") (pintype "passive"))
      (node (ref "C24") (pin "1") (pinfunction "1_1") (pintype "passive"))
      (node (ref "C25") (pin "2") (pinfunction "2_2") (pintype "passive"))
      (node (ref "C27") (pin "1") (pinfunction "1_1") (pintype "passive"))
      (node (ref "C29") (pin "2") (pinfunction "2_2") (pintype "passive"))
      (node (ref "C3") (pin "2") (pinfunction "2_2") (pintype "passive"))
      (node (ref "C30") (pin "2") (pinfunction "2_2") (pintype "passive"))
      (node (ref "C31") (pin "2") (pinfunction "2_2") (pintype "passive"))
      (node (ref "C32") (pin "1") (pinfunction "1_1") (pintype "passive"))
      (node (ref "C33") (pin "2") (pinfunction "2_2") (pintype "passive"))
      (node (ref "C34") (pin "1") (pinfunction "1_1") (pintype "passive"))
      (node (ref "C37") (pin "1") (pinfunction "1_1") (pintype "passive"))
      (node (ref "C38") (pin "1") (pinfunction "1_1") (pintype "passive"))
      (node (ref "C39") (pin "2") (pinfunction "2_2") (pintype "passive"))
      (node (ref "C4") (pin "2") (pinfunction "2_2") (pintype "passive"))
      (node (ref "C42") (pin "2") (pinfunction "2_2") (pintype "passive"))
      (node (ref "C43") (pin "2") (pinfunction "2_2") (pintype "passive"))
      (node (ref "C5") (pin "2") (pinfunction "2_2") (pintype "passive"))
      (node (ref "C6") (pin "2") (pinfunction "2_2") (pintype "passive"))
      (node (ref "C7") (pin "2") (pinfunction "2_2") (pintype "passive"))
      (node (ref "C8") (pin "2") (pinfunction "2_2") (pintype "passive"))
      (node (ref "C9") (pin "2") (pinfunction "2_2") (pintype "passive"))
      (node (ref "D3") (pin "2") (pinfunction "GND_2") (pintype "bidirectional"))
      (node (ref "D4") (pin "1") (pinfunction "K_1") (pintype "bidirectional"))
      (node (ref "EPD_C1") (pin "1") (pinfunction "1_1") (pintype "passive"))
      (node (ref "EPD_C10") (pin "1") (pinfunction "1_1") (pintype "passive"))
      (node (ref "EPD_C11") (pin "1") (pinfunction "1_1") (pintype "passive"))
      (node (ref "EPD_C12") (pin "1") (pinfunction "1_1") (pintype "passive"))
      (node (ref "EPD_C2") (pin "1") (pinfunction "1_1") (pintype "passive"))
      (node (ref "EPD_C5") (pin "1") (pinfunction "1_1") (pintype "passive"))
      (node (ref "EPD_C6") (pin "1") (pinfunction "1_1") (pintype "passive"))
      (node (ref "EPD_C7") (pin "1") (pinfunction "1_1") (pintype "passive"))
      (node (ref "EPD_C8") (pin "1") (pinfunction "1_1") (pintype "passive"))
      (node (ref "EPD_C9") (pin "1") (pinfunction "1_1") (pintype "passive"))
      (node (ref "IC1") (pin "D2") (pinfunction "GND_D2") (pintype "bidirectional"))
      (node (ref "IC2") (pin "B1") (pinfunction "IN/TRIG_B1") (pintype "bidirectional"))
      (node (ref "IC2") (pin "B3") (pinfunction "GND_B3") (pintype "bidirectional"))
      (node (ref "IC3") (pin "8") (pinfunction "GNDIO_8") (pintype "bidirectional"))
      (node (ref "IC3") (pin "9") (pinfunction "GND_9") (pintype "bidirectional"))
      (node (ref "IC9") (pin "B1") (pinfunction "VSEL_B1") (pintype "bidirectional"))
      (node (ref "IC9") (pin "C1") (pinfunction "AGND_C1") (pintype "bidirectional"))
      (node (ref "IC9") (pin "C2") (pinfunction "PGND_1_C2") (pintype "bidirectional"))
      (node (ref "IC9") (pin "C3") (pinfunction "PGND_2_C3") (pintype "bidirectional"))
      (node (ref "J1") (pin "17") (pinfunction "17_17") (pintype "bidirectional"))
      (node (ref "J1") (pin "8") (pinfunction "8_8") (pintype "bidirectional"))
      (node (ref "J1") (pin "MP1") (pinfunction "MP1_MP1") (pintype "bidirectional"))
      (node (ref "J1") (pin "MP2") (pinfunction "MP2_MP2") (pintype "bidirectional"))
      (node (ref "J2") (pin "3") (pinfunction "3_3") (pintype "bidirectional"))
      (node (ref "J2") (pin "5") (pinfunction "5_5") (pintype "bidirectional"))
      (node (ref "J4") (pin "A12_B1") (pinfunction "GND_A12_B1") (pintype "power_in"))
      (node (ref "J4") (pin "A1_B12") (pinfunction "GND_A1_B12") (pintype "power_in"))
      (node (ref "J4") (pin "SH1") (pinfunction "SHIELD_SH1") (pintype "passive"))
      (node (ref "J4") (pin "SH2") (pinfunction "SHIELD_SH2") (pintype "passive"))
      (node (ref "J4") (pin "SH3") (pinfunction "SHIELD_SH3") (pintype "passive"))
      (node (ref "J4") (pin "SH4") (pinfunction "SHIELD_SH4") (pintype "passive"))
      (node (ref "R1_USB") (pin "1") (pinfunction "1_1") (pintype "bidirectional"))
      (node (ref "R2_EP_DR") (pin "1") (pinfunction "1_1") (pintype "bidirectional"))
      (node (ref "R2_USB") (pin "2") (pinfunction "2_2") (pintype "bidirectional"))
      (node (ref "R3") (pin "1") (pinfunction "1_1") (pintype "bidirectional"))
      (node (ref "R9") (pin "1") (pinfunction "1_1") (pintype "bidirectional"))
      (node (ref "R_TYPE_SEL") (pin "1") (pinfunction "1_1") (pintype "bidirectional"))
      (node (ref "SJ1") (pin "1") (pinfunction "1_1") (pintype "passive"))
      (node (ref "SW_DN") (pin "1") (pinfunction "1_1") (pintype "passive"))
      (node (ref "SW_ENT") (pin "1") (pinfunction "1_1") (pintype "passive"))
      (node (ref "SW_UP") (pin "1") (pinfunction "1_1") (pintype "passive"))
      (node (ref "TP_BAT_GND") (pin "TP") (pinfunction "TP_TP") (pintype "input"))
      (node (ref "TP_GND") (pin "TP") (pinfunction "TP_TP") (pintype "input"))
      (node (ref "U1") (pin "P$74") (pinfunction "VSS_PAD_P$74") (pintype "bidirectional"))
      (node (ref "U1") (pin "P$75") (pinfunction "VSS_PAD_P$75") (pintype "bidirectional"))
      (node (ref "U1") (pin "P$76") (pinfunction "VSS_PAD_P$76") (pintype "bidirectional"))
      (node (ref "U1") (pin "P$77") (pinfunction "VSS_PAD_P$77") (pintype "bidirectional"))
      (node (ref "U1") (pin "P$78") (pinfunction "VSS_PAD_P$78") (pintype "bidirectional"))
      (node (ref "U1") (pin "P$79") (pinfunction "VSS_PAD_P$79") (pintype "bidirectional"))
      (node (ref "U1") (pin "P$80") (pinfunction "VSS_PAD_P$80") (pintype "bidirectional"))
      (node (ref "U1") (pin "P$81") (pinfunction "VSS_PAD_P$81") (pintype "bidirectional"))
      (node (ref "U1") (pin "P$82") (pinfunction "VSS_PAD_P$82") (pintype "bidirectional"))
      (node (ref "U1") (pin "P$83") (pinfunction "VSS_PAD_P$83") (pintype "bidirectional"))
      (node (ref "U1") (pin "P$84") (pinfunction "VSS_PAD_P$84") (pintype "bidirectional"))
      (node (ref "U1") (pin "P$85") (pinfunction "VSS_PAD_P$85") (pintype "bidirectional"))
      (node (ref "U1") (pin "P$86") (pinfunction "VSS_PAD_P$86") (pintype "bidirectional"))
      (node (ref "U1") (pin "P$87") (pinfunction "VSS_PAD_P$87") (pintype "bidirectional"))
      (node (ref "U1") (pin "P$88") (pinfunction "VSS_PAD_P$88") (pintype "bidirectional"))
      (node (ref "U1") (pin "P$89") (pinfunction "VSS_PAD_P$89") (pintype "bidirectional"))
      (node (ref "U1") (pin "P$90") (pinfunction "VSS_PAD_P$90") (pintype "bidirectional"))
      (node (ref "U1") (pin "P$B7") (pinfunction "VSS_P$B7") (pintype "power_in"))
      (node (ref "U1") (pin "P$F23") (pinfunction "VSS_PA_P$F23") (pintype "bidirectional"))
      (node (ref "U3") (pin "1") (pinfunction "CTG_1") (pintype "power_in"))
      (node (ref "U3") (pin "4") (pinfunction "GND_4") (pintype "power_in"))
      (node (ref "U3") (pin "6") (pinfunction "QSTRT_6") (pintype "input"))
      (node (ref "U3") (pin "9") (pinfunction "EP_9") (pintype "power_in"))
      (node (ref "X1") (pin "2") (pinfunction "2_2") (pintype "passive"))
      (node (ref "X1") (pin "4") (pinfunction "4_4") (pintype "passive"))
    )
    (net (code "17") (name "HAPTIC_EN") (class "Default")
      (node (ref "IC2") (pin "A1") (pinfunction "EN_A1") (pintype "bidirectional"))
      (node (ref "U1") (pin "P$U1") (pinfunction "P0.12_P$U1") (pintype "bidirectional"))
    )
    (net (code "18") (name "IMU_INT1") (class "Default")
      (node (ref "IC3") (pin "5") (pinfunction "INT1_5") (pintype "bidirectional"))
      (node (ref "U1") (pin "P$N1") (pinfunction "P0.08_P$N1") (pintype "bidirectional"))
    )
    (net (code "19") (name "IMU_INT2") (class "Default")
      (node (ref "IC3") (pin "6") (pinfunction "INT2_6") (pintype "bidirectional"))
      (node (ref "U1") (pin "P$P2") (pinfunction "P1.08_P$P2") (pintype "bidirectional"))
    )
    (net (code "20") (name "LX1") (class "Default")
      (node (ref "IC9") (pin "B2") (pinfunction "SW1_1_B2") (pintype "bidirectional"))
      (node (ref "IC9") (pin "B3") (pinfunction "SW1_2_B3") (pintype "bidirectional"))
      (node (ref "L7") (pin "1") (pinfunction "1_1") (pintype "bidirectional"))
    )
    (net (code "21") (name "LX2") (class "Default")
      (node (ref "IC9") (pin "D2") (pinfunction "SW2_1_D2") (pintype "bidirectional"))
      (node (ref "IC9") (pin "D3") (pinfunction "SW2_2_D3") (pintype "bidirectional"))
      (node (ref "L7") (pin "2") (pinfunction "2_2") (pintype "bidirectional"))
    )
    (net (code "22") (name "MOSI") (class "Default")
      (node (ref "J1") (pin "14") (pinfunction "14_14") (pintype "bidirectional"))
      (node (ref "U1") (pin "P$B13") (pinfunction "P0.03/AIN1_P$B13") (pintype "bidirectional"))
    )
    (net (code "23") (name "Net-(ANT1-FEED)") (class "Default")
      (node (ref "ANT1") (pin "1") (pinfunction "FEED_1") (pintype "input"))
      (node (ref "C22") (pin "1") (pinfunction "1_1") (pintype "passive"))
      (node (ref "C4") (pin "1") (pinfunction "1_1") (pintype "passive"))
      (node (ref "L1") (pin "1") (pinfunction "1_1") (pintype "bidirectional"))
    )
    (net (code "24") (name "Net-(D2-K)") (class "Default")
      (node (ref "C2-EP-DR") (pin "1") (pinfunction "1_1") (pintype "passive"))
      (node (ref "D2") (pin "1") (pinfunction "K_1") (pintype "bidirectional"))
      (node (ref "D4") (pin "2") (pinfunction "A_2") (pintype "bidirectional"))
    )
    (net (code "25") (name "Net-(D5-A)") (class "Default")
      (node (ref "C2-EP-DR") (pin "2") (pinfunction "2_2") (pintype "passive"))
      (node (ref "D5") (pin "2") (pinfunction "A_2") (pintype "bidirectional"))
      (node (ref "L5") (pin "1") (pinfunction "1_1") (pintype "passive"))
      (node (ref "Q3") (pin "3") (pinfunction "D_3") (pintype "bidirectional"))
    )
    (net (code "26") (name "Net-(EPD_C1-Pad2)") (class "Default")
      (node (ref "EPD_C1") (pin "2") (pinfunction "2_2") (pintype "passive"))
      (node (ref "J1") (pin "5") (pinfunction "5_5") (pintype "bidirectional"))
    )
    (net (code "27") (name "Net-(EPD_C2-Pad2)") (class "Default")
      (node (ref "EPD_C2") (pin "2") (pinfunction "2_2") (pintype "passive"))
      (node (ref "J1") (pin "4") (pinfunction "4_4") (pintype "bidirectional"))
    )
    (net (code "28") (name "Net-(EPD_C6-Pad2)") (class "Default")
      (node (ref "EPD_C6") (pin "2") (pinfunction "2_2") (pintype "passive"))
      (node (ref "J1") (pin "18") (pinfunction "18_18") (pintype "bidirectional"))
    )
    (net (code "29") (name "Net-(EPD_C7-Pad2)") (class "Default")
      (node (ref "EPD_C7") (pin "2") (pinfunction "2_2") (pintype "passive"))
      (node (ref "J1") (pin "19") (pinfunction "19_19") (pintype "bidirectional"))
    )
    (net (code "30") (name "Net-(EPD_C8-Pad2)") (class "Default")
      (node (ref "EPD_C8") (pin "2") (pinfunction "2_2") (pintype "passive"))
      (node (ref "J1") (pin "20") (pinfunction "20_20") (pintype "bidirectional"))
    )
    (net (code "31") (name "Net-(EPD_C10-Pad2)") (class "Default")
      (node (ref "EPD_C10") (pin "2") (pinfunction "2_2") (pintype "passive"))
      (node (ref "J1") (pin "22") (pinfunction "22_22") (pintype "bidirectional"))
    )
    (net (code "32") (name "Net-(EPD_C12-Pad2)") (class "Default")
      (node (ref "EPD_C12") (pin "2") (pinfunction "2_2") (pintype "passive"))
      (node (ref "J1") (pin "24") (pinfunction "24_24") (pintype "bidirectional"))
    )
    (net (code "33") (name "Net-(IC1-TS{slash}MR)") (class "Default")
      (node (ref "IC1") (pin "D1") (pinfunction "TS/MR_D1") (pintype "bidirectional"))
      (node (ref "R9") (pin "2") (pinfunction "2_2") (pintype "bidirectional"))
    )
    (net (code "34") (name "Net-(IC2-REG)") (class "Default")
      (node (ref "C32") (pin "2") (pinfunction "2_2") (pintype "passive"))
      (node (ref "IC2") (pin "A2") (pinfunction "REG_A2") (pintype "bidirectional"))
    )
    (net (code "35") (name "Net-(IC3-SDO)") (class "Default")
      (node (ref "IC3") (pin "1") (pinfunction "SDO_1") (pintype "bidirectional"))
      (node (ref "R3") (pin "2") (pinfunction "2_2") (pintype "bidirectional"))
    )
    (net (code "36") (name "Net-(IC9-SCL)") (class "Default")
      (node (ref "IC9") (pin "D1") (pinfunction "SCL_D1") (pintype "bidirectional"))
      (node (ref "R4") (pin "2") (pinfunction "2_2") (pintype "bidirectional"))
    )
    (net (code "37") (name "Net-(IC9-SDA)") (class "Default")
      (node (ref "IC9") (pin "E1") (pinfunction "SDA_E1") (pintype "bidirectional"))
      (node (ref "R2") (pin "2") (pinfunction "2_2") (pintype "bidirectional"))
    )
    (net (code "38") (name "Net-(J4-CC1)") (class "Default")
      (node (ref "J4") (pin "A5") (pinfunction "CC1_A5") (pintype "bidirectional"))
      (node (ref "R1_USB") (pin "2") (pinfunction "2_2") (pintype "bidirectional"))
    )
    (net (code "39") (name "Net-(J4-CC2)") (class "Default")
      (node (ref "J4") (pin "B5") (pinfunction "CC2_B5") (pintype "bidirectional"))
      (node (ref "R2_USB") (pin "1") (pinfunction "1_1") (pintype "bidirectional"))
    )
    (net (code "40") (name "Net-(L2-Pad2)") (class "Default")
      (node (ref "L2") (pin "2") (pinfunction "2_2") (pintype "bidirectional"))
      (node (ref "L3") (pin "1") (pinfunction "1_1") (pintype "bidirectional"))
    )
    (net (code "41") (name "Net-(R1_EP_DR-Pad1)") (class "Default")
      (node (ref "R1_EP_DR") (pin "1") (pinfunction "1_1") (pintype "bidirectional"))
      (node (ref "R_TYPE_SEL") (pin "2") (pinfunction "2_2") (pintype "bidirectional"))
      (node (ref "SJ1") (pin "2") (pinfunction "2_2") (pintype "passive"))
    )
    (net (code "42") (name "Net-(U1-ANT)") (class "Default")
      (node (ref "C3") (pin "1") (pinfunction "1_1") (pintype "passive"))
      (node (ref "L1") (pin "2") (pinfunction "2_2") (pintype "bidirectional"))
      (node (ref "U1") (pin "P$H23") (pinfunction "ANT_P$H23") (pintype "bidirectional"))
    )
    (net (code "43") (name "Net-(U1-DCC)") (class "Default")
      (node (ref "L2") (pin "1") (pinfunction "1_1") (pintype "bidirectional"))
      (node (ref "U1") (pin "P$B3") (pinfunction "DCC_P$B3") (pintype "output"))
    )
    (net (code "44") (name "Net-(U1-DEC2)") (class "Default")
      (node (ref "C13") (pin "1") (pinfunction "1_1") (pintype "passive"))
      (node (ref "U1") (pin "P$A18") (pinfunction "DEC2_P$A18") (pintype "bidirectional"))
    )
    (net (code "45") (name "Net-(U1-DEC3V3)") (class "Default")
      (node (ref "C20") (pin "1") (pinfunction "1_1") (pintype "passive"))
      (node (ref "U1") (pin "P$AC5") (pinfunction "DEC3V3_P$AC5") (pintype "bidirectional"))
    )
    (net (code "46") (name "Net-(U1-DEC5)") (class "Default")
      (node (ref "C9") (pin "1") (pinfunction "1_1") (pintype "passive"))
      (node (ref "U1") (pin "P$N24") (pinfunction "DEC5_P$N24") (pintype "bidirectional"))
    )
    (net (code "47") (name "Net-(U1-XC1)") (class "Default")
      (node (ref "C1") (pin "1") (pinfunction "1_1") (pintype "passive"))
      (node (ref "U1") (pin "P$B24") (pinfunction "XC1_P$B24") (pintype "input"))
      (node (ref "X1") (pin "1") (pinfunction "1_1") (pintype "passive"))
    )
    (net (code "48") (name "Net-(U1-XC2)") (class "Default")
      (node (ref "C2") (pin "1") (pinfunction "1_1") (pintype "passive"))
      (node (ref "U1") (pin "P$A23") (pinfunction "XC2_P$A23") (pintype "output"))
      (node (ref "X1") (pin "3") (pinfunction "3_3") (pintype "passive"))
    )
    (net (code "49") (name "OUT+") (class "Default")
      (node (ref "IC2") (pin "A3") (pinfunction "OUT+_A3") (pintype "bidirectional"))
      (node (ref "TP_OP") (pin "TP") (pinfunction "TP_TP") (pintype "input"))
    )
    (net (code "50") (name "OUT-") (class "Default")
      (node (ref "IC2") (pin "C3") (pinfunction "OUT-_C3") (pintype "bidirectional"))
      (node (ref "TP_ON") (pin "TP") (pinfunction "TP_TP") (pintype "input"))
    )
    (net (code "51") (name "P0.00{slash}XL1") (class "Default")
      (node (ref "C17") (pin "2") (pinfunction "2_2") (pintype "passive"))
      (node (ref "U1") (pin "P$D2") (pinfunction "P0.00/XL1_P$D2") (pintype "bidirectional"))
      (node (ref "X2") (pin "1") (pinfunction "1_1") (pintype "passive"))
    )
    (net (code "52") (name "P0.01{slash}XL2") (class "Default")
      (node (ref "C18") (pin "2") (pinfunction "2_2") (pintype "passive"))
      (node (ref "U1") (pin "P$F2") (pinfunction "P0.01/XL2_P$F2") (pintype "bidirectional"))
      (node (ref "X2") (pin "2") (pinfunction "2_2") (pintype "passive"))
    )
    (net (code "53") (name "P0.04") (class "Default")
      (node (ref "U1") (pin "P$J1") (pinfunction "P0.04/AIN2_P$J1") (pintype "bidirectional"))
    )
    (net (code "54") (name "P0.09") (class "Default")
      (node (ref "U1") (pin "P$L24") (pinfunction "P0.09/NFC1_P$L24") (pintype "bidirectional"))
    )
    (net (code "55") (name "P0.13") (class "Default")
      (node (ref "C30") (pin "1") (pinfunction "1_1") (pintype "passive"))
      (node (ref "R5") (pin "1") (pinfunction "1_1") (pintype "bidirectional"))
      (node (ref "SW_UP") (pin "2") (pinfunction "2_2") (pintype "passive"))
      (node (ref "U1") (pin "P$AD8") (pinfunction "P0.13_P$AD8") (pintype "bidirectional"))
    )
    (net (code "56") (name "P0.14") (class "Default")
      (node (ref "C31") (pin "1") (pinfunction "1_1") (pintype "passive"))
      (node (ref "R8") (pin "1") (pinfunction "1_1") (pintype "bidirectional"))
      (node (ref "SW_ENT") (pin "2") (pinfunction "2_2") (pintype "passive"))
      (node (ref "U1") (pin "P$AC9") (pinfunction "P0.14_P$AC9") (pintype "bidirectional"))
    )
    (net (code "57") (name "P0.19") (class "Default")
      (node (ref "U1") (pin "P$AC15") (pinfunction "P0.19_P$AC15") (pintype "bidirectional"))
    )
    (net (code "58") (name "P0.20") (class "Default")
      (node (ref "U1") (pin "P$AD16") (pinfunction "P0.20_P$AD16") (pintype "bidirectional"))
    )
    (net (code "59") (name "P0.21") (class "Default")
      (node (ref "U1") (pin "P$AC17") (pinfunction "P0.21_P$AC17") (pintype "bidirectional"))
    )
    (net (code "60") (name "P0.22") (class "Default")
      (node (ref "U1") (pin "P$AD18") (pinfunction "P0.22_P$AD18") (pintype "bidirectional"))
    )
    (net (code "61") (name "P0.23") (class "Default")
      (node (ref "U1") (pin "P$AC19") (pinfunction "P0.23_P$AC19") (pintype "bidirectional"))
    )
    (net (code "62") (name "P0.24") (class "Default")
      (node (ref "U1") (pin "P$AD20") (pinfunction "P0.24_P$AD20") (pintype "bidirectional"))
    )
    (net (code "63") (name "P0.25") (class "Default")
      (node (ref "U1") (pin "P$AC21") (pinfunction "P0.25_P$AC21") (pintype "bidirectional"))
    )
    (net (code "64") (name "P0.26") (class "Default")
      (node (ref "U1") (pin "P$G1") (pinfunction "P0.26_P$G1") (pintype "bidirectional"))
    )
    (net (code "65") (name "P0.27") (class "Default")
      (node (ref "U1") (pin "P$H2") (pinfunction "P0.27_P$H2") (pintype "bidirectional"))
    )
    (net (code "66") (name "P0.28") (class "Default")
      (node (ref "U1") (pin "P$B11") (pinfunction "P0.28/AIN4_P$B11") (pintype "bidirectional"))
    )
    (net (code "67") (name "P0.29") (class "Default")
      (node (ref "U1") (pin "P$A10") (pinfunction "P0.29/AIN5_P$A10") (pintype "bidirectional"))
    )
    (net (code "68") (name "P0.30") (class "Default")
      (node (ref "U1") (pin "P$B9") (pinfunction "P0.30/AIN6_P$B9") (pintype "bidirectional"))
    )
    (net (code "69") (name "P0.31") (class "Default")
      (node (ref "U1") (pin "P$A8") (pinfunction "P0.31/AIN7_P$A8") (pintype "bidirectional"))
    )
    (net (code "70") (name "P1.01") (class "Default")
      (node (ref "Q1") (pin "1") (pinfunction "G_1") (pintype "bidirectional"))
      (node (ref "R_PWR_EPD") (pin "1") (pinfunction "1_1") (pintype "bidirectional"))
      (node (ref "U1") (pin "P$Y23") (pinfunction "P1.01_P$Y23") (pintype "bidirectional"))
    )
    (net (code "71") (name "P1.02") (class "Default")
      (node (ref "C29") (pin "1") (pinfunction "1_1") (pintype "passive"))
      (node (ref "R7") (pin "1") (pinfunction "1_1") (pintype "bidirectional"))
      (node (ref "SW_DN") (pin "2") (pinfunction "2_2") (pintype "passive"))
      (node (ref "U1") (pin "P$W24") (pinfunction "P1.02_P$W24") (pintype "bidirectional"))
    )
    (net (code "72") (name "P1.03") (class "Default")
      (node (ref "U1") (pin "P$V23") (pinfunction "P1.03_P$V23") (pintype "bidirectional"))
    )
    (net (code "73") (name "P1.04") (class "Default")
      (node (ref "U1") (pin "P$U24") (pinfunction "P1.04_P$U24") (pintype "bidirectional"))
    )
    (net (code "74") (name "P1.05") (class "Default")
      (node (ref "U1") (pin "P$T23") (pinfunction "P1.05_P$T23") (pintype "bidirectional"))
    )
    (net (code "75") (name "P1.06") (class "Default")
      (node (ref "U1") (pin "P$R24") (pinfunction "P1.06_P$R24") (pintype "bidirectional"))
    )
    (net (code "76") (name "P1.07") (class "Default")
      (node (ref "U1") (pin "P$P23") (pinfunction "P1.07_P$P23") (pintype "bidirectional"))
    )
    (net (code "77") (name "P1.09") (class "Default")
      (node (ref "U1") (pin "P$R1") (pinfunction "P1.09_P$R1") (pintype "bidirectional"))
    )
    (net (code "78") (name "P1.10") (class "Default")
      (node (ref "U1") (pin "P$A20") (pinfunction "P1.10_P$A20") (pintype "bidirectional"))
    )
    (net (code "79") (name "P1.11") (class "Default")
      (node (ref "U1") (pin "P$B19") (pinfunction "P1.11_P$B19") (pintype "bidirectional"))
    )
    (net (code "80") (name "P1.12") (class "Default")
      (node (ref "U1") (pin "P$B17") (pinfunction "P1.12_P$B17") (pintype "bidirectional"))
    )
    (net (code "81") (name "P1.13") (class "Default")
      (node (ref "U1") (pin "P$A16") (pinfunction "P1.13_P$A16") (pintype "bidirectional"))
    )
    (net (code "82") (name "P1.14") (class "Default")
      (node (ref "U1") (pin "P$B15") (pinfunction "P1.14_P$B15") (pintype "bidirectional"))
    )
    (net (code "83") (name "P1.15") (class "Default")
      (node (ref "U1") (pin "P$A14") (pinfunction "P1.15_P$A14") (pintype "bidirectional"))
    )
    (net (code "84") (name "PMIC_INT") (class "Default")
      (node (ref "IC1") (pin "A1") (pinfunction "~{INT}_A1") (pintype "bidirectional"))
      (node (ref "U1") (pin "P$T2") (pinfunction "P0.11_P$T2") (pintype "bidirectional"))
    )
    (net (code "85") (name "PREVGH") (class "Default")
      (node (ref "D5") (pin "1") (pinfunction "K_1") (pintype "bidirectional"))
      (node (ref "EPD_C9") (pin "2") (pinfunction "2_2") (pintype "passive"))
      (node (ref "J1") (pin "21") (pinfunction "21_21") (pintype "bidirectional"))
    )
    (net (code "86") (name "PREVGL") (class "Default")
      (node (ref "D2") (pin "2") (pinfunction "A_2") (pintype "bidirectional"))
      (node (ref "EPD_C11") (pin "2") (pinfunction "2_2") (pintype "passive"))
      (node (ref "J1") (pin "23") (pinfunction "23_23") (pintype "bidirectional"))
    )
    (net (code "87") (name "RESE") (class "Default")
      (node (ref "J1") (pin "3") (pinfunction "3_3") (pintype "bidirectional"))
      (node (ref "Q3") (pin "2") (pinfunction "S_2") (pintype "bidirectional"))
      (node (ref "R1_EP_DR") (pin "2") (pinfunction "2_2") (pintype "bidirectional"))
    )
    (net (code "88") (name "RESET") (class "Default")
      (node (ref "J2") (pin "6") (pinfunction "6_6") (pintype "bidirectional"))
      (node (ref "TP_RESET") (pin "TP") (pinfunction "TP_TP") (pintype "input"))
      (node (ref "U1") (pin "P$AC13") (pinfunction "P0.18/RESET_P$AC13") (pintype "bidirectional"))
    )
    (net (code "89") (name "SCK") (class "Default")
      (node (ref "J1") (pin "13") (pinfunction "13_13") (pintype "bidirectional"))
      (node (ref "U1") (pin "P$A12") (pinfunction "P0.02/AIN0_P$A12") (pintype "bidirectional"))
    )
    (net (code "90") (name "SCL") (class "Default")
      (node (ref "C34") (pin "2") (pinfunction "2_2") (pintype "passive"))
      (node (ref "IC1") (pin "B1") (pinfunction "SCL_B1") (pintype "bidirectional"))
      (node (ref "IC2") (pin "C1") (pinfunction "SCL_C1") (pintype "bidirectional"))
      (node (ref "IC3") (pin "12") (pinfunction "SCX_12") (pintype "bidirectional"))
      (node (ref "R17") (pin "2") (pinfunction "2_2") (pintype "bidirectional"))
      (node (ref "R4") (pin "1") (pinfunction "1_1") (pintype "bidirectional"))
      (node (ref "TP_SCL") (pin "TP") (pinfunction "TP_TP") (pintype "input"))
      (node (ref "U1") (pin "P$M2") (pinfunction "P0.07_P$M2") (pintype "bidirectional"))
      (node (ref "U3") (pin "7") (pinfunction "SCL_7") (pintype "input"))
    )
    (net (code "91") (name "SDA") (class "Default")
      (node (ref "IC1") (pin "C1") (pinfunction "SDA_C1") (pintype "bidirectional"))
      (node (ref "IC2") (pin "B2") (pinfunction "SDA_B2") (pintype "bidirectional"))
      (node (ref "IC3") (pin "2") (pinfunction "SDX_2") (pintype "bidirectional"))
      (node (ref "R18") (pin "2") (pinfunction "2_2") (pintype "bidirectional"))
      (node (ref "R2") (pin "1") (pinfunction "1_1") (pintype "bidirectional"))
      (node (ref "TP_SDA") (pin "TP") (pinfunction "TP_TP") (pintype "input"))
      (node (ref "U1") (pin "P$L1") (pinfunction "P0.06_P$L1") (pintype "bidirectional"))
      (node (ref "U3") (pin "8") (pinfunction "SDA_8") (pintype "bidirectional"))
    )
    (net (code "92") (name "SWDCLK") (class "Default")
      (node (ref "J2") (pin "4") (pinfunction "4_4") (pintype "bidirectional"))
      (node (ref "TP_SWDCLK") (pin "TP") (pinfunction "TP_TP") (pintype "input"))
      (node (ref "U1") (pin "P$AA24") (pinfunction "SWDCLK_P$AA24") (pintype "input"))
    )
    (net (code "93") (name "SWDIO") (class "Default")
      (node (ref "J2") (pin "2") (pinfunction "2_2") (pintype "bidirectional"))
      (node (ref "TP_SWDIO") (pin "TP") (pinfunction "TP_TP") (pintype "input"))
      (node (ref "U1") (pin "P$AC24") (pinfunction "SWDIO_P$AC24") (pintype "bidirectional"))
    )
    (net (code "94") (name "SWO") (class "Default")
      (node (ref "TP_SWO") (pin "TP") (pinfunction "TP_TP") (pintype "input"))
      (node (ref "U1") (pin "P$AD22") (pinfunction "P1.00_P$AD22") (pintype "bidirectional"))
    )
    (net (code "95") (name "VBAT") (class "Default")
      (node (ref "C27") (pin "2") (pinfunction "2_2") (pintype "passive"))
      (node (ref "C37") (pin "2") (pinfunction "2_2") (pintype "passive"))
      (node (ref "IC1") (pin "C2") (pinfunction "BAT_C2") (pintype "bidirectional"))
      (node (ref "TP_VBAT") (pin "TP") (pinfunction "TP_TP") (pintype "input"))
      (node (ref "U3") (pin "2") (pinfunction "CELL_2") (pintype "power_in"))
      (node (ref "U3") (pin "3") (pinfunction "VDD_3") (pintype "power_in"))
    )
    (net (code "96") (name "VBUS") (class "Default")
      (node (ref "C21") (pin "1") (pinfunction "1_1") (pintype "passive"))
      (node (ref "C38") (pin "2") (pinfunction "2_2") (pintype "passive"))
      (node (ref "C42") (pin "1") (pinfunction "1_1") (pintype "passive"))
      (node (ref "C43") (pin "1") (pinfunction "1_1") (pintype "passive"))
      (node (ref "D3") (pin "5") (pinfunction "VBUS_5") (pintype "bidirectional"))
      (node (ref "IC1") (pin "A2") (pinfunction "IN_A2") (pintype "bidirectional"))
      (node (ref "J4") (pin "A4_B9") (pinfunction "VBUS_A4_B9") (pintype "power_in"))
      (node (ref "J4") (pin "A9_B4") (pinfunction "VBUS_A9_B4") (pintype "power_in"))
      (node (ref "U1") (pin "P$AD2") (pinfunction "VBUS_P$AD2") (pintype "power_in"))
    )
    (net (code "97") (name "VREG") (class "Default")
      (node (ref "C23") (pin "2") (pinfunction "2_2") (pintype "passive"))
      (node (ref "C24") (pin "2") (pinfunction "2_2") (pintype "passive"))
      (node (ref "C39") (pin "1") (pinfunction "1_1") (pintype "passive"))
      (node (ref "IC1") (pin "B2") (pinfunction "SYS_B2") (pintype "bidirectional"))
      (node (ref "IC9") (pin "A1") (pinfunction "EN_A1") (pintype "bidirectional"))
      (node (ref "IC9") (pin "A2") (pinfunction "VIN_1_A2") (pintype "bidirectional"))
      (node (ref "IC9") (pin "A3") (pinfunction "VIN_2_A3") (pintype "bidirectional"))
      (node (ref "TP_VREG") (pin "TP") (pinfunction "TP_TP") (pintype "input"))
    )
    (net (code "98") (name "unconnected-(ANT1-NC-Pad2)") (class "Default")
      (node (ref "ANT1") (pin "2") (pinfunction "NC_2") (pintype "no_connect"))
    )
    (net (code "99") (name "unconnected-(IC3-ASCL-Pad11)") (class "Default")
      (node (ref "IC3") (pin "11") (pinfunction "ASCL_11") (pintype "bidirectional"))
    )
    (net (code "100") (name "unconnected-(IC3-ASDA-Pad4)") (class "Default")
      (node (ref "IC3") (pin "4") (pinfunction "ASDA_4") (pintype "bidirectional"))
    )
    (net (code "101") (name "unconnected-(J1-Pad1)") (class "Default")
      (node (ref "J1") (pin "1") (pinfunction "1_1") (pintype "bidirectional"))
    )
    (net (code "102") (name "unconnected-(J1-Pad6)") (class "Default")
      (node (ref "J1") (pin "6") (pinfunction "6_6") (pintype "bidirectional"))
    )
    (net (code "103") (name "unconnected-(J1-Pad7)") (class "Default")
      (node (ref "J1") (pin "7") (pinfunction "7_7") (pintype "bidirectional"))
    )
    (net (code "104") (name "unconnected-(J4-SBU1-PadA8)") (class "Default")
      (node (ref "J4") (pin "A8") (pinfunction "SBU1_A8") (pintype "bidirectional"))
    )
    (net (code "105") (name "unconnected-(J4-SBU2-PadB8)") (class "Default")
      (node (ref "J4") (pin "B8") (pinfunction "SBU2_B8") (pintype "bidirectional"))
    )
    (net (code "106") (name "unconnected-(U1-DCCH-PadP$AB2)") (class "Default")
      (node (ref "U1") (pin "P$AB2") (pinfunction "DCCH_P$AB2") (pintype "bidirectional"))
    )
  )
)
